# Sheet1.net
KiCad netlist of a schematic drawn in Altium Designer
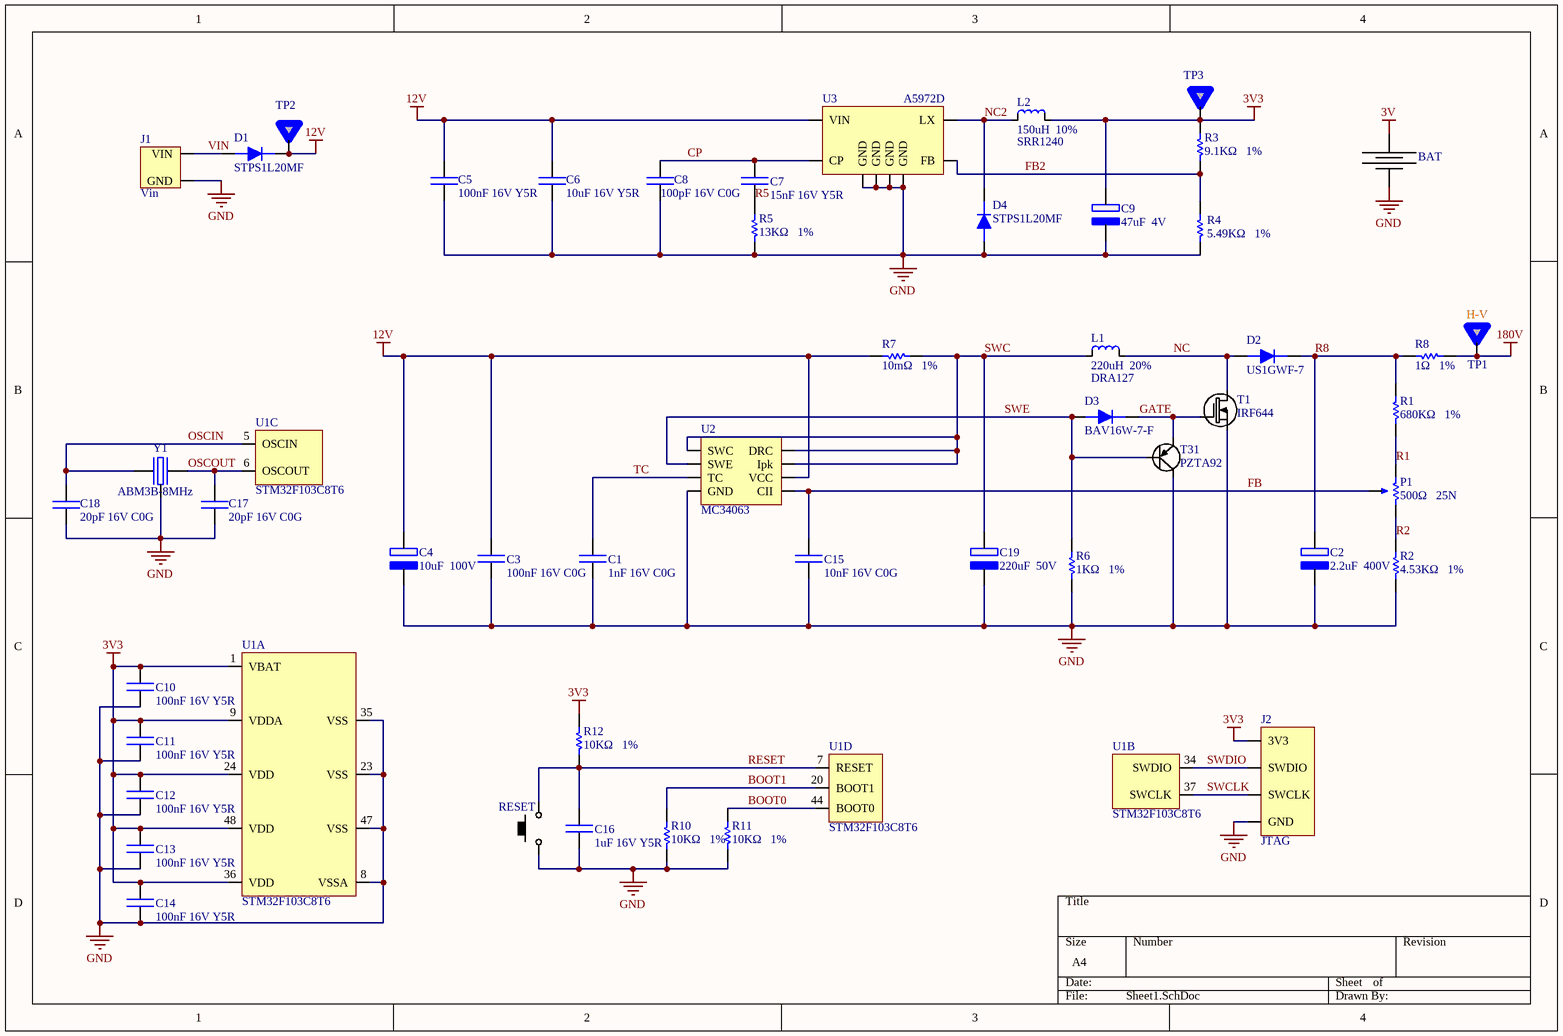
[diagram p0: Sheet1.SchDoc]

(export (version "E")
  (design (tool "Eeschema 10.0.6"))
  (components
    (comp (ref "BAT") (value "3V") (footprint "HOLDER-2032") (libsource (lib "Nixielib") (part "BAT")))
    (comp (ref "C1") (value "1nF 16V C0G") (footprint "0603") (libsource (lib "Nixielib") (part "CAP")))
    (comp (ref "C2")
      (value "2.2uF  400V")
      (footprint "CAP-SIZE-F")
      (libsource (lib "Nixielib") (part "CAP_pol"))
    )
    (comp (ref "C3") (value "100nF 16V C0G") (footprint "0603") (libsource (lib "Nixielib") (part "CAP")))
    (comp (ref "C4")
      (value "10uF  100V")
      (footprint "CAP-SIZE-F")
      (libsource (lib "Nixielib") (part "CAP_pol"))
    )
    (comp (ref "C5") (value "100nF 16V Y5R") (footprint "0603") (libsource (lib "Nixielib") (part "CAP")))
    (comp (ref "C6") (value "10uF 16V Y5R") (footprint "0603") (libsource (lib "Nixielib") (part "CAP")))
    (comp (ref "C7") (value "15nF 16V Y5R") (footprint "0603") (libsource (lib "Nixielib") (part "CAP")))
    (comp (ref "C8") (value "100pF 16V C0G") (footprint "0603") (libsource (lib "Nixielib") (part "CAP")))
    (comp (ref "C9")
      (value "47uF  4V")
      (footprint "AVX-B-CASE")
      (libsource (lib "Nixielib") (part "CAP_pol"))
    )
    (comp (ref "C10") (value "100nF 16V Y5R") (footprint "0603") (libsource (lib "Nixielib") (part "CAP")))
    (comp (ref "C11") (value "100nF 16V Y5R") (footprint "0603") (libsource (lib "Nixielib") (part "CAP")))
    (comp (ref "C12") (value "100nF 16V Y5R") (footprint "0603") (libsource (lib "Nixielib") (part "CAP")))
    (comp (ref "C13") (value "100nF 16V Y5R") (footprint "0603") (libsource (lib "Nixielib") (part "CAP")))
    (comp (ref "C14") (value "100nF 16V Y5R") (footprint "0603") (libsource (lib "Nixielib") (part "CAP")))
    (comp (ref "C15") (value "10nF 16V C0G") (footprint "0603") (libsource (lib "Nixielib") (part "CAP")))
    (comp (ref "C16") (value "1uF 16V Y5R") (footprint "0603") (libsource (lib "Nixielib") (part "CAP")))
    (comp (ref "C17") (value "20pF 16V C0G") (footprint "0603") (libsource (lib "Nixielib") (part "CAP")))
    (comp (ref "C18") (value "20pF 16V C0G") (footprint "0603") (libsource (lib "Nixielib") (part "CAP")))
    (comp (ref "C19")
      (value "220uF  50V")
      (footprint "CAP-SIZE-F")
      (libsource (lib "Nixielib") (part "CAP_pol"))
    )
    (comp (ref "D1") (value "STPS1L20MF") (footprint "DO-222AA") (libsource (lib "Nixielib") (part "DIO")))
    (comp (ref "D2") (value "US1GWF-7") (footprint "SOD-123F") (libsource (lib "Nixielib") (part "DIO")))
    (comp (ref "D3") (value "BAV16W-7-F") (footprint "SOD-123F") (libsource (lib "Nixielib") (part "DIO")))
    (comp (ref "D4") (value "STPS1L20MF") (footprint "DO-222AA") (libsource (lib "Nixielib") (part "DIO")))
    (comp (ref "J1") (value "Vin") (footprint "BORNERAx2") (libsource (lib "Nixielib") (part "Vin")))
    (comp (ref "J2") (value "JTAG") (footprint "PIN-HEADERx4") (libsource (lib "Nixielib") (part "JTAG")))
    (comp (ref "L1") (value "220uH  20%") (footprint "DRA127") (libsource (lib "Nixielib") (part "IND")))
    (comp (ref "L2") (value "150uH  10%") (footprint "SRR1240") (libsource (lib "Nixielib") (part "IND")))
    (comp (ref "P1") (value "500Ω   25N") (footprint "3296W") (libsource (lib "Nixielib") (part "POTE")))
    (comp (ref "R1") (value "680KΩ   1%") (footprint "0603") (libsource (lib "Nixielib") (part "RES")))
    (comp (ref "R2") (value "4.53KΩ   1%") (footprint "0603") (libsource (lib "Nixielib") (part "RES")))
    (comp (ref "R3") (value "9.1KΩ   1%") (footprint "0603") (libsource (lib "Nixielib") (part "RES")))
    (comp (ref "R4") (value "5.49KΩ   1%") (footprint "0603") (libsource (lib "Nixielib") (part "RES")))
    (comp (ref "R5") (value "13KΩ   1%") (footprint "0603") (libsource (lib "Nixielib") (part "RES")))
    (comp (ref "R6") (value "1KΩ   1%") (footprint "0603") (libsource (lib "Nixielib") (part "RES")))
    (comp (ref "R7") (value "10mΩ   1%") (footprint "0603") (libsource (lib "Nixielib") (part "RES")))
    (comp (ref "R8") (value "1Ω   1%") (footprint "0603") (libsource (lib "Nixielib") (part "RES")))
    (comp (ref "R10") (value "10KΩ   1%") (footprint "0603") (libsource (lib "Nixielib") (part "RES")))
    (comp (ref "R11") (value "10KΩ   1%") (footprint "0603") (libsource (lib "Nixielib") (part "RES")))
    (comp (ref "R12") (value "10KΩ   1%") (footprint "0603") (libsource (lib "Nixielib") (part "RES")))
    (comp (ref "RESET") (value "RESET") (footprint "FSMSM") (libsource (lib "Nixielib") (part "BUTTON")))
    (comp (ref "T1") (value "IRF644") (footprint "TO263-3S") (libsource (lib "Nixielib") (part "N-MOS")))
    (comp (ref "T31") (value "PZTA92") (footprint "SOT-23") (libsource (lib "Nixielib") (part "PNP")))
    (comp (ref "TP1")
      (value "HV-TEST-POINT")
      (footprint "Test_Point_HV")
      (libsource (lib "Nixielib") (part "HV-TEST-POINT"))
    )
    (comp (ref "TP2")
      (value "TEST-POINT")
      (footprint "Test_Point")
      (libsource (lib "Nixielib") (part "TEST-POINT"))
    )
    (comp (ref "TP3")
      (value "TEST-POINT")
      (footprint "Test_Point")
      (libsource (lib "Nixielib") (part "TEST-POINT"))
    )
    (comp (ref "U1")
      (value "STM32F103C8T6")
      (footprint "LQFP48")
      (libsource (lib "Nixielib") (part "STM32F103C8T6"))
    )
    (comp (ref "U2") (value "MC34063") (footprint "SOIC-8") (libsource (lib "Nixielib") (part "MC34063")))
    (comp (ref "U3") (value "A5972D") (footprint "SOIC-8") (libsource (lib "Nixielib") (part "A5972D")))
    (comp (ref "Y1") (value "ABM3B-8MHz") (footprint "ABM3B") (libsource (lib "Nixielib") (part "Cristal")))
  )
  (nets
    (net (code "1") (name "/BOOT0") (class "Default")
      (node (ref "R11") (pin "2") (pinfunction "2_2") (pintype "passive"))
      (node (ref "U1") (pin "44") (pinfunction "BOOT0_44") (pintype "passive"))
    )
    (net (code "2") (name "/BOOT1") (class "Default")
      (node (ref "R10") (pin "2") (pinfunction "2_2") (pintype "passive"))
      (node (ref "U1") (pin "20") (pinfunction "BOOT1_20") (pintype "passive"))
    )
    (net (code "3") (name "/CP") (class "Default")
      (node (ref "C7") (pin "2") (pinfunction "2_2") (pintype "passive"))
      (node (ref "C8") (pin "2") (pinfunction "2_2") (pintype "passive"))
      (node (ref "U3") (pin "4") (pinfunction "CP_4") (pintype "passive"))
    )
    (net (code "4") (name "/FB") (class "Default")
      (node (ref "C15") (pin "2") (pinfunction "2_2") (pintype "passive"))
      (node (ref "P1") (pin "2") (pinfunction "2_2") (pintype "passive"))
      (node (ref "U2") (pin "5") (pinfunction "CII_5") (pintype "passive"))
    )
    (net (code "5") (name "/FB2") (class "Default")
      (node (ref "R3") (pin "1") (pinfunction "1_1") (pintype "passive"))
      (node (ref "R4") (pin "1") (pinfunction "1_1") (pintype "passive"))
      (node (ref "U3") (pin "5") (pinfunction "FB_5") (pintype "passive"))
    )
    (net (code "6") (name "/GATE") (class "Default")
      (node (ref "D3") (pin "2") (pinfunction "2_2") (pintype "passive"))
      (node (ref "T1") (pin "1") (pinfunction "G_1") (pintype "passive"))
      (node (ref "T31") (pin "2") (pinfunction "E_2") (pintype "passive"))
    )
    (net (code "7") (name "/NC") (class "Default")
      (node (ref "D2") (pin "1") (pinfunction "1_1") (pintype "passive"))
      (node (ref "L1") (pin "2") (pinfunction "2_2") (pintype "passive"))
      (node (ref "T1") (pin "3") (pinfunction "D_3") (pintype "passive"))
    )
    (net (code "8") (name "/NC2") (class "Default")
      (node (ref "D4") (pin "2") (pinfunction "2_2") (pintype "passive"))
      (node (ref "L2") (pin "1") (pinfunction "1_1") (pintype "passive"))
      (node (ref "U3") (pin "1") (pinfunction "LX_1") (pintype "passive"))
    )
    (net (code "9") (name "/OSCIN") (class "Default")
      (node (ref "C18") (pin "2") (pinfunction "2_2") (pintype "passive"))
      (node (ref "U1") (pin "5") (pinfunction "OSCIN_5") (pintype "passive"))
      (node (ref "Y1") (pin "1") (pinfunction "1_1") (pintype "passive"))
    )
    (net (code "10") (name "/OSCOUT") (class "Default")
      (node (ref "C17") (pin "2") (pinfunction "2_2") (pintype "passive"))
      (node (ref "U1") (pin "6") (pinfunction "OSCOUT_6") (pintype "passive"))
      (node (ref "Y1") (pin "2") (pinfunction "2_2") (pintype "passive"))
    )
    (net (code "11") (name "/R1") (class "Default")
      (node (ref "P1") (pin "3") (pinfunction "3_3") (pintype "passive"))
      (node (ref "R1") (pin "1") (pinfunction "1_1") (pintype "passive"))
    )
    (net (code "12") (name "/R2") (class "Default")
      (node (ref "P1") (pin "1") (pinfunction "1_1") (pintype "passive"))
      (node (ref "R2") (pin "2") (pinfunction "2_2") (pintype "passive"))
    )
    (net (code "13") (name "/R5") (class "Default")
      (node (ref "C7") (pin "1") (pinfunction "1_1") (pintype "passive"))
      (node (ref "R5") (pin "2") (pinfunction "2_2") (pintype "passive"))
    )
    (net (code "14") (name "/R8") (class "Default")
      (node (ref "C2") (pin "2") (pinfunction "2_2") (pintype "passive"))
      (node (ref "D2") (pin "2") (pinfunction "2_2") (pintype "passive"))
      (node (ref "R1") (pin "2") (pinfunction "2_2") (pintype "passive"))
      (node (ref "R8") (pin "1") (pinfunction "1_1") (pintype "passive"))
    )
    (net (code "15") (name "/RESET") (class "Default")
      (node (ref "C16") (pin "2") (pinfunction "2_2") (pintype "passive"))
      (node (ref "R12") (pin "1") (pinfunction "1_1") (pintype "passive"))
      (node (ref "RESET") (pin "1") (pinfunction "1_1") (pintype "passive"))
      (node (ref "U1") (pin "7") (pinfunction "RESET_7") (pintype "passive"))
    )
    (net (code "16") (name "/SWC") (class "Default")
      (node (ref "C19") (pin "2") (pinfunction "2_2") (pintype "passive"))
      (node (ref "L1") (pin "1") (pinfunction "1_1") (pintype "passive"))
      (node (ref "R7") (pin "2") (pinfunction "2_2") (pintype "passive"))
      (node (ref "U2") (pin "1") (pinfunction "SWC_1") (pintype "passive"))
      (node (ref "U2") (pin "7") (pinfunction "Ipk_7") (pintype "passive"))
      (node (ref "U2") (pin "8") (pinfunction "DRC_8") (pintype "passive"))
    )
    (net (code "17") (name "/SWCLK") (class "Default")
      (node (ref "J2") (pin "3") (pinfunction "SWCLK_3") (pintype "passive"))
      (node (ref "U1") (pin "37") (pinfunction "SWCLK_37") (pintype "passive"))
    )
    (net (code "18") (name "/SWDIO") (class "Default")
      (node (ref "J2") (pin "2") (pinfunction "SWDIO_2") (pintype "passive"))
      (node (ref "U1") (pin "34") (pinfunction "SWDIO_34") (pintype "passive"))
    )
    (net (code "19") (name "/SWE") (class "Default")
      (node (ref "D3") (pin "1") (pinfunction "1_1") (pintype "passive"))
      (node (ref "R6") (pin "2") (pinfunction "2_2") (pintype "passive"))
      (node (ref "T31") (pin "1") (pinfunction "B_1") (pintype "passive"))
      (node (ref "U2") (pin "2") (pinfunction "SWE_2") (pintype "passive"))
    )
    (net (code "20") (name "/TC") (class "Default")
      (node (ref "C1") (pin "2") (pinfunction "2_2") (pintype "passive"))
      (node (ref "U2") (pin "3") (pinfunction "TC_3") (pintype "passive"))
    )
    (net (code "21") (name "/VIN") (class "Default")
      (node (ref "D1") (pin "1") (pinfunction "1_1") (pintype "passive"))
      (node (ref "J1") (pin "1") (pinfunction "VIN_1") (pintype "passive"))
    )
    (net (code "22") (name "3V") (class "Default")
      (node (ref "BAT") (pin "1") (pinfunction "+_1") (pintype "passive"))
    )
    (net (code "23") (name "3V3") (class "Default")
      (node (ref "C10") (pin "1") (pinfunction "1_1") (pintype "passive"))
      (node (ref "C11") (pin "1") (pinfunction "1_1") (pintype "passive"))
      (node (ref "C12") (pin "1") (pinfunction "1_1") (pintype "passive"))
      (node (ref "C13") (pin "1") (pinfunction "1_1") (pintype "passive"))
      (node (ref "C14") (pin "1") (pinfunction "1_1") (pintype "passive"))
      (node (ref "C9") (pin "2") (pinfunction "2_2") (pintype "passive"))
      (node (ref "J2") (pin "1") (pinfunction "3V3_1") (pintype "passive"))
      (node (ref "L2") (pin "2") (pinfunction "2_2") (pintype "passive"))
      (node (ref "R12") (pin "2") (pinfunction "2_2") (pintype "passive"))
      (node (ref "R3") (pin "2") (pinfunction "2_2") (pintype "passive"))
      (node (ref "TP3") (pin "1") (pinfunction "1_1") (pintype "passive"))
      (node (ref "U1") (pin "1") (pinfunction "VBAT_1") (pintype "passive"))
      (node (ref "U1") (pin "24") (pinfunction "VDD_24") (pintype "passive"))
      (node (ref "U1") (pin "36") (pinfunction "VDD_36") (pintype "passive"))
      (node (ref "U1") (pin "48") (pinfunction "VDD_48") (pintype "passive"))
      (node (ref "U1") (pin "9") (pinfunction "VDDA_9") (pintype "passive"))
    )
    (net (code "24") (name "12V") (class "Default")
      (node (ref "C3") (pin "2") (pinfunction "2_2") (pintype "passive"))
      (node (ref "C4") (pin "2") (pinfunction "2_2") (pintype "passive"))
      (node (ref "C5") (pin "2") (pinfunction "2_2") (pintype "passive"))
      (node (ref "C6") (pin "2") (pinfunction "2_2") (pintype "passive"))
      (node (ref "D1") (pin "2") (pinfunction "2_2") (pintype "passive"))
      (node (ref "R7") (pin "1") (pinfunction "1_1") (pintype "passive"))
      (node (ref "TP2") (pin "1") (pinfunction "1_1") (pintype "passive"))
      (node (ref "U2") (pin "6") (pinfunction "VCC_6") (pintype "passive"))
      (node (ref "U3") (pin "8") (pinfunction "VIN_8") (pintype "passive"))
    )
    (net (code "25") (name "180V") (class "Default")
      (node (ref "R8") (pin "2") (pinfunction "2_2") (pintype "passive"))
      (node (ref "TP1") (pin "1") (pinfunction "1_1") (pintype "passive"))
    )
    (net (code "26") (name "GND") (class "Default")
      (node (ref "BAT") (pin "2") (pinfunction "-_2") (pintype "passive"))
      (node (ref "C1") (pin "1") (pinfunction "1_1") (pintype "passive"))
      (node (ref "C10") (pin "2") (pinfunction "2_2") (pintype "passive"))
      (node (ref "C11") (pin "2") (pinfunction "2_2") (pintype "passive"))
      (node (ref "C12") (pin "2") (pinfunction "2_2") (pintype "passive"))
      (node (ref "C13") (pin "2") (pinfunction "2_2") (pintype "passive"))
      (node (ref "C14") (pin "2") (pinfunction "2_2") (pintype "passive"))
      (node (ref "C15") (pin "1") (pinfunction "1_1") (pintype "passive"))
      (node (ref "C16") (pin "1") (pinfunction "1_1") (pintype "passive"))
      (node (ref "C17") (pin "1") (pinfunction "1_1") (pintype "passive"))
      (node (ref "C18") (pin "1") (pinfunction "1_1") (pintype "passive"))
      (node (ref "C19") (pin "1") (pinfunction "1_1") (pintype "passive"))
      (node (ref "C2") (pin "1") (pinfunction "1_1") (pintype "passive"))
      (node (ref "C3") (pin "1") (pinfunction "1_1") (pintype "passive"))
      (node (ref "C4") (pin "1") (pinfunction "1_1") (pintype "passive"))
      (node (ref "C5") (pin "1") (pinfunction "1_1") (pintype "passive"))
      (node (ref "C6") (pin "1") (pinfunction "1_1") (pintype "passive"))
      (node (ref "C8") (pin "1") (pinfunction "1_1") (pintype "passive"))
      (node (ref "C9") (pin "1") (pinfunction "1_1") (pintype "passive"))
      (node (ref "D4") (pin "1") (pinfunction "1_1") (pintype "passive"))
      (node (ref "J1") (pin "2") (pinfunction "GND_2") (pintype "passive"))
      (node (ref "J2") (pin "4") (pinfunction "GND_4") (pintype "passive"))
      (node (ref "R10") (pin "1") (pinfunction "1_1") (pintype "passive"))
      (node (ref "R11") (pin "1") (pinfunction "1_1") (pintype "passive"))
      (node (ref "R2") (pin "1") (pinfunction "1_1") (pintype "passive"))
      (node (ref "R4") (pin "2") (pinfunction "2_2") (pintype "passive"))
      (node (ref "R5") (pin "1") (pinfunction "1_1") (pintype "passive"))
      (node (ref "R6") (pin "1") (pinfunction "1_1") (pintype "passive"))
      (node (ref "RESET") (pin "2") (pinfunction "2_2") (pintype "passive"))
      (node (ref "T1") (pin "2") (pinfunction "S_2") (pintype "passive"))
      (node (ref "T31") (pin "3") (pinfunction "C_3") (pintype "passive"))
      (node (ref "U1") (pin "23") (pinfunction "VSS_23") (pintype "passive"))
      (node (ref "U1") (pin "35") (pinfunction "VSS_35") (pintype "passive"))
      (node (ref "U1") (pin "47") (pinfunction "VSS_47") (pintype "passive"))
      (node (ref "U1") (pin "8") (pinfunction "VSSA_8") (pintype "passive"))
      (node (ref "U2") (pin "4") (pinfunction "GND_4") (pintype "passive"))
      (node (ref "U3") (pin "2") (pinfunction "GND_2") (pintype "passive"))
      (node (ref "U3") (pin "3") (pinfunction "GND_3") (pintype "passive"))
      (node (ref "U3") (pin "6") (pinfunction "GND_6") (pintype "passive"))
      (node (ref "U3") (pin "7") (pinfunction "GND_7") (pintype "passive"))
      (node (ref "Y1") (pin "3") (pinfunction "3_3") (pintype "passive"))
    )
  )
)
